# Sheet1.net
KiCad netlist of a schematic drawn in Altium Designer
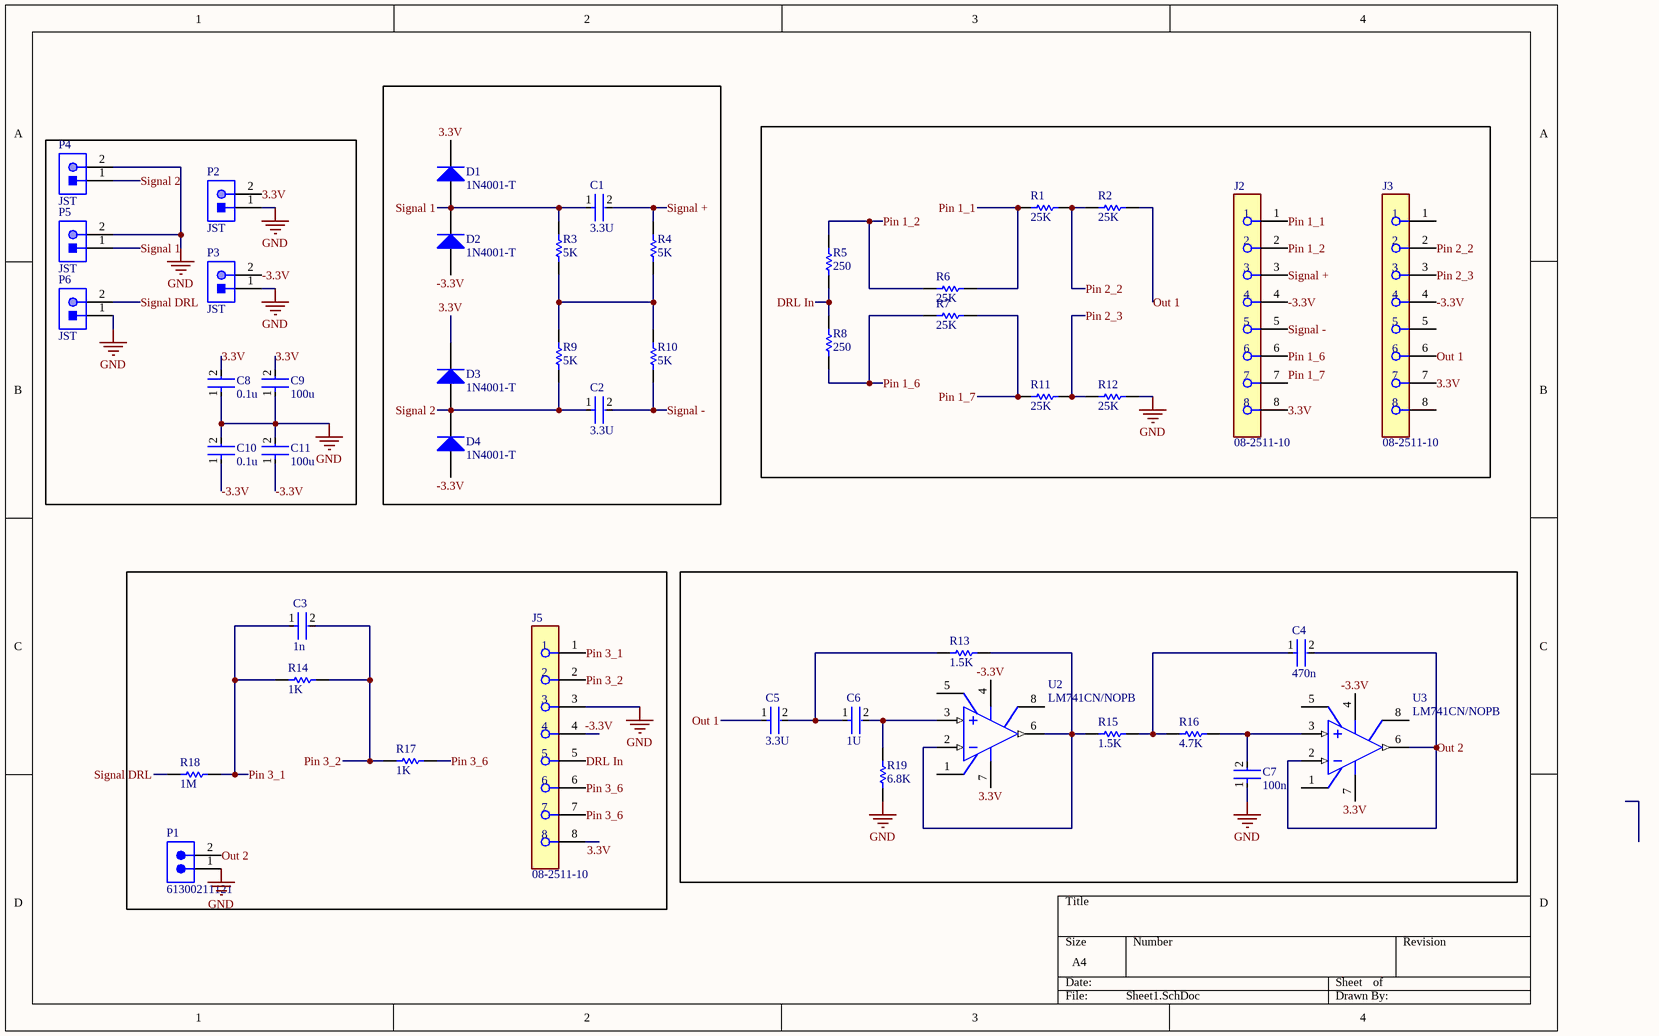
[diagram p0: Sheet1.SchDoc]

(export (version "E")
  (design (tool "Eeschema 10.0.6"))
  (components
    (comp (ref "C1")
      (value "3.3U")
      (footprint "FP-RCE3DB-MFG")
      (description "Cap Ceramic 10uF 25V X7R ±10% Radial 2.5mm +125°C Automotive Ammo Pack")
      (fields (field (name "TOLERANCE") "10%"))
      (libsource (lib "Altium Content Vault") (part "b4654b650e69147ec39a6b967a45e02"))
    )
    (comp (ref "C2")
      (value "3.3U")
      (footprint "FP-RCE3DB-MFG")
      (description "Cap Ceramic 10uF 25V X7R ±10% Radial 2.5mm +125°C Automotive Ammo Pack")
      (fields (field (name "TOLERANCE") "10%"))
      (libsource (lib "Altium Content Vault") (part "b4654b650e69147ec39a6b967a45e02"))
    )
    (comp (ref "C3")
      (value "1n")
      (footprint "FP-RCE3DB-MFG")
      (description "Cap Ceramic 10uF 25V X7R ±10% Radial 2.5mm +125°C Automotive Ammo Pack")
      (fields (field (name "TOLERANCE") "10%"))
      (libsource (lib "Altium Content Vault") (part "b4654b650e69147ec39a6b967a45e02"))
    )
    (comp (ref "C4")
      (value "470n")
      (footprint "FP-RCE3DB-MFG")
      (description "Cap Ceramic 10uF 25V X7R ±10% Radial 2.5mm +125°C Automotive Ammo Pack")
      (fields (field (name "TOLERANCE") "10%"))
      (libsource (lib "Altium Content Vault") (part "b4654b650e69147ec39a6b967a45e02"))
    )
    (comp (ref "C5")
      (value "3.3U")
      (footprint "FP-RCE3DB-MFG")
      (description "Cap Ceramic 10uF 25V X7R ±10% Radial 2.5mm +125°C Automotive Ammo Pack")
      (fields (field (name "TOLERANCE") "10%"))
      (libsource (lib "Altium Content Vault") (part "b4654b650e69147ec39a6b967a45e02"))
    )
    (comp (ref "C6")
      (value "1U")
      (footprint "FP-RCE3DB-MFG")
      (description "Cap Ceramic 10uF 25V X7R ±10% Radial 2.5mm +125°C Automotive Ammo Pack")
      (fields (field (name "TOLERANCE") "10%"))
      (libsource (lib "Altium Content Vault") (part "b4654b650e69147ec39a6b967a45e02"))
    )
    (comp (ref "C7")
      (value "100n")
      (footprint "FP-RCE3DB-MFG")
      (description "Cap Ceramic 10uF 25V X7R ±10% Radial 2.5mm +125°C Automotive Ammo Pack")
      (fields (field (name "TOLERANCE") "10%"))
      (libsource (lib "Altium Content Vault") (part "b4654b650e69147ec39a6b967a45e02"))
    )
    (comp (ref "C8")
      (value "0.1u")
      (footprint "FP-RCE3DB-MFG")
      (description "Cap Ceramic 10uF 25V X7R ±10% Radial 2.5mm +125°C Automotive Ammo Pack")
      (fields (field (name "TOLERANCE") "10%"))
      (libsource (lib "Altium Content Vault") (part "b4654b650e69147ec39a6b967a45e02"))
    )
    (comp (ref "C9")
      (value "100u")
      (footprint "FP-RCE3DB-MFG")
      (description "Cap Ceramic 10uF 25V X7R ±10% Radial 2.5mm +125°C Automotive Ammo Pack")
      (fields (field (name "TOLERANCE") "10%"))
      (libsource (lib "Altium Content Vault") (part "b4654b650e69147ec39a6b967a45e02"))
    )
    (comp (ref "C10")
      (value "0.1u")
      (footprint "FP-RCE3DB-MFG")
      (description "Cap Ceramic 10uF 25V X7R ±10% Radial 2.5mm +125°C Automotive Ammo Pack")
      (fields (field (name "TOLERANCE") "10%"))
      (libsource (lib "Altium Content Vault") (part "b4654b650e69147ec39a6b967a45e02"))
    )
    (comp (ref "C11")
      (value "100u")
      (footprint "FP-RCE3DB-MFG")
      (description "Cap Ceramic 10uF 25V X7R ±10% Radial 2.5mm +125°C Automotive Ammo Pack")
      (fields (field (name "TOLERANCE") "10%"))
      (libsource (lib "Altium Content Vault") (part "b4654b650e69147ec39a6b967a45e02"))
    )
    (comp (ref "D1")
      (value "1N4001-T")
      (footprint "DIOD-DO-41-P-2_V")
      (description "1.0 A Rectifier, 15 pF, 50 V, -65 to 150 degC, 2-Pin DO-41 Plastic, RoHS, Tape and Reel")
      (fields (field (name "MANUFACTURER") "Diodes Inc"))
      (libsource (lib "Altium Content Vault") (part "DIOD-D-A1K2-2"))
    )
    (comp (ref "D2")
      (value "1N4001-T")
      (footprint "DIOD-DO-41-P-2_V")
      (description "1.0 A Rectifier, 15 pF, 50 V, -65 to 150 degC, 2-Pin DO-41 Plastic, RoHS, Tape and Reel")
      (fields (field (name "MANUFACTURER") "Diodes Inc"))
      (libsource (lib "Altium Content Vault") (part "DIOD-D-A1K2-2"))
    )
    (comp (ref "D3")
      (value "1N4001-T")
      (footprint "DIOD-DO-41-P-2_V")
      (description "1.0 A Rectifier, 15 pF, 50 V, -65 to 150 degC, 2-Pin DO-41 Plastic, RoHS, Tape and Reel")
      (fields (field (name "MANUFACTURER") "Diodes Inc"))
      (libsource (lib "Altium Content Vault") (part "DIOD-D-A1K2-2"))
    )
    (comp (ref "D4")
      (value "1N4001-T")
      (footprint "DIOD-DO-41-P-2_V")
      (description "1.0 A Rectifier, 15 pF, 50 V, -65 to 150 degC, 2-Pin DO-41 Plastic, RoHS, Tape and Reel")
      (fields (field (name "MANUFACTURER") "Diodes Inc"))
      (libsource (lib "Altium Content Vault") (part "DIOD-D-A1K2-2"))
    )
    (comp (ref "J2")
      (value "08-2511-10")
      (footprint "FP-08-2511-10-MFG")
      (description "CONN IC DIP SOCKET 8POS TIN")
      (fields
        (field (name "MANUFACTURER") "Aries Electronics")
        (field (name "OCTOPART") "https://octopart.com/08-2511-10-aries-767661")
      )
      (libsource (lib "Altium Content Vault") (part "b0a0b555dd3abf3683e7c330df25cc4"))
    )
    (comp (ref "J3")
      (value "08-2511-10")
      (footprint "FP-08-2511-10-MFG")
      (description "CONN IC DIP SOCKET 8POS TIN")
      (fields
        (field (name "MANUFACTURER") "Aries Electronics")
        (field (name "OCTOPART") "https://octopart.com/08-2511-10-aries-767661")
      )
      (libsource (lib "Altium Content Vault") (part "b0a0b555dd3abf3683e7c330df25cc4"))
    )
    (comp (ref "J5")
      (value "08-2511-10")
      (footprint "FP-08-2511-10-MFG")
      (description "CONN IC DIP SOCKET 8POS TIN")
      (fields
        (field (name "MANUFACTURER") "Aries Electronics")
        (field (name "OCTOPART") "https://octopart.com/08-2511-10-aries-767661")
      )
      (libsource (lib "Altium Content Vault") (part "b0a0b555dd3abf3683e7c330df25cc4"))
    )
    (comp (ref "P1")
      (value "61300211121")
      (footprint "61300211121")
      (libsource (lib "Altium Content Vault") (part "Header_Male_1R_02P"))
    )
    (comp (ref "P2")
      (value "JST")
      (footprint "JST-S2B-PH-K-S_V")
      (fields (field (name "TOLERANCE") "20%"))
      (libsource (lib "Altium Content Vault") (part "CN-1P-M-R2"))
    )
    (comp (ref "P3")
      (value "JST")
      (footprint "JST-S2B-PH-K-S_V")
      (fields (field (name "TOLERANCE") "20%"))
      (libsource (lib "Altium Content Vault") (part "CN-1P-M-R2"))
    )
    (comp (ref "P4")
      (value "JST")
      (footprint "JST-S2B-PH-K-S_V")
      (fields (field (name "TOLERANCE") "20%"))
      (libsource (lib "Altium Content Vault") (part "CN-1P-M-R2"))
    )
    (comp (ref "P5")
      (value "JST")
      (footprint "JST-S2B-PH-K-S_V")
      (fields (field (name "TOLERANCE") "20%"))
      (libsource (lib "Altium Content Vault") (part "CN-1P-M-R2"))
    )
    (comp (ref "P6")
      (value "JST")
      (footprint "JST-S2B-PH-K-S_V")
      (fields (field (name "TOLERANCE") "20%"))
      (libsource (lib "Altium Content Vault") (part "CN-1P-M-R2"))
    )
    (comp (ref "R1")
      (value "25K")
      (footprint "RESA60-630X240")
      (description "Axial Resistor, 1 KOhm, +/- 1%, 250 mW, -55 to 155 degC, 2-Pin THD, RoHS, Bulk")
      (fields (field (name "TOLERANCE") "1%"))
      (libsource (lib "Altium Content Vault") (part "RES-2"))
    )
    (comp (ref "R2")
      (value "25K")
      (footprint "RESA60-630X240")
      (description "Axial Resistor, 1 KOhm, +/- 1%, 250 mW, -55 to 155 degC, 2-Pin THD, RoHS, Bulk")
      (fields (field (name "TOLERANCE") "1%"))
      (libsource (lib "Altium Content Vault") (part "RES-2"))
    )
    (comp (ref "R3")
      (value "5K")
      (footprint "RESA60-630X240")
      (description "Axial Resistor, 1 KOhm, +/- 1%, 250 mW, -55 to 155 degC, 2-Pin THD, RoHS, Bulk")
      (fields (field (name "TOLERANCE") "1%"))
      (libsource (lib "Altium Content Vault") (part "RES-2"))
    )
    (comp (ref "R4")
      (value "5K")
      (footprint "RESA60-630X240")
      (description "Axial Resistor, 1 KOhm, +/- 1%, 250 mW, -55 to 155 degC, 2-Pin THD, RoHS, Bulk")
      (fields (field (name "TOLERANCE") "1%"))
      (libsource (lib "Altium Content Vault") (part "RES-2"))
    )
    (comp (ref "R5")
      (value "250")
      (footprint "RESA60-630X240")
      (description "Axial Resistor, 1 KOhm, +/- 1%, 250 mW, -55 to 155 degC, 2-Pin THD, RoHS, Bulk")
      (fields (field (name "TOLERANCE") "1%"))
      (libsource (lib "Altium Content Vault") (part "RES-2"))
    )
    (comp (ref "R6")
      (value "25K")
      (footprint "RESA60-630X240")
      (description "Axial Resistor, 1 KOhm, +/- 1%, 250 mW, -55 to 155 degC, 2-Pin THD, RoHS, Bulk")
      (fields (field (name "TOLERANCE") "1%"))
      (libsource (lib "Altium Content Vault") (part "RES-2"))
    )
    (comp (ref "R7")
      (value "25K")
      (footprint "RESA60-630X240")
      (description "Axial Resistor, 1 KOhm, +/- 1%, 250 mW, -55 to 155 degC, 2-Pin THD, RoHS, Bulk")
      (fields (field (name "TOLERANCE") "1%"))
      (libsource (lib "Altium Content Vault") (part "RES-2"))
    )
    (comp (ref "R8")
      (value "250")
      (footprint "RESA60-630X240")
      (description "Axial Resistor, 1 KOhm, +/- 1%, 250 mW, -55 to 155 degC, 2-Pin THD, RoHS, Bulk")
      (fields (field (name "TOLERANCE") "1%"))
      (libsource (lib "Altium Content Vault") (part "RES-2"))
    )
    (comp (ref "R9")
      (value "5K")
      (footprint "RESA60-630X240")
      (description "Axial Resistor, 1 KOhm, +/- 1%, 250 mW, -55 to 155 degC, 2-Pin THD, RoHS, Bulk")
      (fields (field (name "TOLERANCE") "1%"))
      (libsource (lib "Altium Content Vault") (part "RES-2"))
    )
    (comp (ref "R10")
      (value "5K")
      (footprint "RESA60-630X240")
      (description "Axial Resistor, 1 KOhm, +/- 1%, 250 mW, -55 to 155 degC, 2-Pin THD, RoHS, Bulk")
      (fields (field (name "TOLERANCE") "1%"))
      (libsource (lib "Altium Content Vault") (part "RES-2"))
    )
    (comp (ref "R11")
      (value "25K")
      (footprint "RESA60-630X240")
      (description "Axial Resistor, 1 KOhm, +/- 1%, 250 mW, -55 to 155 degC, 2-Pin THD, RoHS, Bulk")
      (fields (field (name "TOLERANCE") "1%"))
      (libsource (lib "Altium Content Vault") (part "RES-2"))
    )
    (comp (ref "R12")
      (value "25K")
      (footprint "RESA60-630X240")
      (description "Axial Resistor, 1 KOhm, +/- 1%, 250 mW, -55 to 155 degC, 2-Pin THD, RoHS, Bulk")
      (fields (field (name "TOLERANCE") "1%"))
      (libsource (lib "Altium Content Vault") (part "RES-2"))
    )
    (comp (ref "R13")
      (value "1.5K")
      (footprint "RESA60-630X240")
      (description "Axial Resistor, 1 KOhm, +/- 1%, 250 mW, -55 to 155 degC, 2-Pin THD, RoHS, Bulk")
      (fields (field (name "TOLERANCE") "1%"))
      (libsource (lib "Altium Content Vault") (part "RES-2"))
    )
    (comp (ref "R14")
      (value "1K")
      (footprint "RESA60-630X240")
      (description "Axial Resistor, 1 KOhm, +/- 1%, 250 mW, -55 to 155 degC, 2-Pin THD, RoHS, Bulk")
      (fields (field (name "TOLERANCE") "1%"))
      (libsource (lib "Altium Content Vault") (part "RES-2"))
    )
    (comp (ref "R15")
      (value "1.5K")
      (footprint "RESA60-630X240")
      (description "Axial Resistor, 1 KOhm, +/- 1%, 250 mW, -55 to 155 degC, 2-Pin THD, RoHS, Bulk")
      (fields (field (name "TOLERANCE") "1%"))
      (libsource (lib "Altium Content Vault") (part "RES-2"))
    )
    (comp (ref "R16")
      (value "4.7K")
      (footprint "RESA60-630X240")
      (description "Axial Resistor, 1 KOhm, +/- 1%, 250 mW, -55 to 155 degC, 2-Pin THD, RoHS, Bulk")
      (fields (field (name "TOLERANCE") "1%"))
      (libsource (lib "Altium Content Vault") (part "RES-2"))
    )
    (comp (ref "R17")
      (value "1K")
      (footprint "RESA60-630X240")
      (description "Axial Resistor, 1 KOhm, +/- 1%, 250 mW, -55 to 155 degC, 2-Pin THD, RoHS, Bulk")
      (fields (field (name "TOLERANCE") "1%"))
      (libsource (lib "Altium Content Vault") (part "RES-2"))
    )
    (comp (ref "R18")
      (value "1M")
      (footprint "RESA60-630X240")
      (description "Axial Resistor, 1 KOhm, +/- 1%, 250 mW, -55 to 155 degC, 2-Pin THD, RoHS, Bulk")
      (fields (field (name "TOLERANCE") "1%"))
      (libsource (lib "Altium Content Vault") (part "RES-2"))
    )
    (comp (ref "R19")
      (value "6.8K")
      (footprint "RESA60-630X240")
      (description "Axial Resistor, 1 KOhm, +/- 1%, 250 mW, -55 to 155 degC, 2-Pin THD, RoHS, Bulk")
      (fields (field (name "TOLERANCE") "1%"))
      (libsource (lib "Altium Content Vault") (part "RES-2"))
    )
    (comp (ref "U2")
      (value "LM741CN/NOPB")
      (footprint "P0008A")
      (description "Operational Amplifier, 8-pin MDIP, Pb-Free")
      (fields (field (name "MANUFACTURER") "Texas Instruments"))
      (libsource (lib "Altium Content Vault") (part "AMP-OPA-LM741-8"))
    )
    (comp (ref "U3")
      (value "LM741CN/NOPB")
      (footprint "P0008A")
      (description "Operational Amplifier, 8-pin MDIP, Pb-Free")
      (fields (field (name "MANUFACTURER") "Texas Instruments"))
      (libsource (lib "Altium Content Vault") (part "AMP-OPA-LM741-8"))
    )
  )
  (nets
    (net (code "1") (name "/-3.3V") (class "Default")
      (node (ref "C10") (pin "1") (pinfunction "1_1") (pintype "passive"))
      (node (ref "C11") (pin "1") (pinfunction "1_1") (pintype "passive"))
      (node (ref "D2") (pin "1") (pinfunction "A_1") (pintype "passive"))
      (node (ref "D4") (pin "1") (pinfunction "A_1") (pintype "passive"))
      (node (ref "J2") (pin "4") (pinfunction "4_4") (pintype "passive"))
      (node (ref "J3") (pin "4") (pinfunction "4_4") (pintype "passive"))
      (node (ref "J5") (pin "4") (pinfunction "4_4") (pintype "passive"))
      (node (ref "P3") (pin "2") (pinfunction "2_2") (pintype "passive"))
      (node (ref "U2") (pin "4") (pinfunction "V-_4") (pintype "power_in"))
      (node (ref "U3") (pin "4") (pinfunction "V-_4") (pintype "power_in"))
    )
    (net (code "2") (name "/3.3V") (class "Default")
      (node (ref "C8") (pin "2") (pinfunction "2_2") (pintype "passive"))
      (node (ref "C9") (pin "2") (pinfunction "2_2") (pintype "passive"))
      (node (ref "D1") (pin "2") (pinfunction "K_2") (pintype "passive"))
      (node (ref "D3") (pin "2") (pinfunction "K_2") (pintype "passive"))
      (node (ref "J2") (pin "8") (pinfunction "8_8") (pintype "passive"))
      (node (ref "J3") (pin "7") (pinfunction "7_7") (pintype "passive"))
      (node (ref "J5") (pin "8") (pinfunction "8_8") (pintype "passive"))
      (node (ref "P2") (pin "2") (pinfunction "2_2") (pintype "passive"))
      (node (ref "U2") (pin "7") (pinfunction "V+_7") (pintype "power_in"))
      (node (ref "U3") (pin "7") (pinfunction "V+_7") (pintype "power_in"))
    )
    (net (code "3") (name "/DRL In") (class "Default")
      (node (ref "J5") (pin "5") (pinfunction "5_5") (pintype "passive"))
      (node (ref "R5") (pin "2") (pinfunction "2_2") (pintype "passive"))
      (node (ref "R8") (pin "1") (pinfunction "1_1") (pintype "passive"))
    )
    (net (code "4") (name "/Out 1") (class "Default")
      (node (ref "C5") (pin "1") (pinfunction "1_1") (pintype "passive"))
      (node (ref "J3") (pin "6") (pinfunction "6_6") (pintype "passive"))
      (node (ref "R2") (pin "1") (pinfunction "1_1") (pintype "passive"))
    )
    (net (code "5") (name "/Out 2") (class "Default")
      (node (ref "C4") (pin "2") (pinfunction "2_2") (pintype "passive"))
      (node (ref "P1") (pin "2") (pinfunction "2_2") (pintype "passive"))
      (node (ref "U3") (pin "2") (pinfunction "IN-_2") (pintype "input"))
      (node (ref "U3") (pin "6") (pinfunction "OUT_6") (pintype "output"))
    )
    (net (code "6") (name "/Pin 1_1") (class "Default")
      (node (ref "J2") (pin "1") (pinfunction "1_1") (pintype "passive"))
      (node (ref "R1") (pin "2") (pinfunction "2_2") (pintype "passive"))
      (node (ref "R6") (pin "1") (pinfunction "1_1") (pintype "passive"))
    )
    (net (code "7") (name "/Pin 1_2") (class "Default")
      (node (ref "J2") (pin "2") (pinfunction "2_2") (pintype "passive"))
      (node (ref "R5") (pin "1") (pinfunction "1_1") (pintype "passive"))
      (node (ref "R6") (pin "2") (pinfunction "2_2") (pintype "passive"))
    )
    (net (code "8") (name "/Pin 1_6") (class "Default")
      (node (ref "J2") (pin "6") (pinfunction "6_6") (pintype "passive"))
      (node (ref "R7") (pin "2") (pinfunction "2_2") (pintype "passive"))
      (node (ref "R8") (pin "2") (pinfunction "2_2") (pintype "passive"))
    )
    (net (code "9") (name "/Pin 1_7") (class "Default")
      (node (ref "J2") (pin "7") (pinfunction "7_7") (pintype "passive"))
      (node (ref "R11") (pin "2") (pinfunction "2_2") (pintype "passive"))
      (node (ref "R7") (pin "1") (pinfunction "1_1") (pintype "passive"))
    )
    (net (code "10") (name "/Pin 2_2") (class "Default")
      (node (ref "J3") (pin "2") (pinfunction "2_2") (pintype "passive"))
      (node (ref "R1") (pin "1") (pinfunction "1_1") (pintype "passive"))
      (node (ref "R2") (pin "2") (pinfunction "2_2") (pintype "passive"))
    )
    (net (code "11") (name "/Pin 2_3") (class "Default")
      (node (ref "J3") (pin "3") (pinfunction "3_3") (pintype "passive"))
      (node (ref "R11") (pin "1") (pinfunction "1_1") (pintype "passive"))
      (node (ref "R12") (pin "2") (pinfunction "2_2") (pintype "passive"))
    )
    (net (code "12") (name "/Pin 3_1") (class "Default")
      (node (ref "C3") (pin "1") (pinfunction "1_1") (pintype "passive"))
      (node (ref "J5") (pin "1") (pinfunction "1_1") (pintype "passive"))
      (node (ref "R14") (pin "2") (pinfunction "2_2") (pintype "passive"))
      (node (ref "R18") (pin "1") (pinfunction "1_1") (pintype "passive"))
    )
    (net (code "13") (name "/Pin 3_2") (class "Default")
      (node (ref "C3") (pin "2") (pinfunction "2_2") (pintype "passive"))
      (node (ref "J5") (pin "2") (pinfunction "2_2") (pintype "passive"))
      (node (ref "R14") (pin "1") (pinfunction "1_1") (pintype "passive"))
      (node (ref "R17") (pin "2") (pinfunction "2_2") (pintype "passive"))
    )
    (net (code "14") (name "/Pin 3_6") (class "Default")
      (node (ref "J5") (pin "6") (pinfunction "6_6") (pintype "passive"))
      (node (ref "J5") (pin "7") (pinfunction "7_7") (pintype "passive"))
      (node (ref "R17") (pin "1") (pinfunction "1_1") (pintype "passive"))
    )
    (net (code "15") (name "/Signal +") (class "Default")
      (node (ref "C1") (pin "2") (pinfunction "2_2") (pintype "passive"))
      (node (ref "J2") (pin "3") (pinfunction "3_3") (pintype "passive"))
      (node (ref "R4") (pin "2") (pinfunction "2_2") (pintype "passive"))
    )
    (net (code "16") (name "/Signal -") (class "Default")
      (node (ref "C2") (pin "2") (pinfunction "2_2") (pintype "passive"))
      (node (ref "J2") (pin "5") (pinfunction "5_5") (pintype "passive"))
      (node (ref "R10") (pin "1") (pinfunction "1_1") (pintype "passive"))
    )
    (net (code "17") (name "/Signal 1") (class "Default")
      (node (ref "C1") (pin "1") (pinfunction "1_1") (pintype "passive"))
      (node (ref "D1") (pin "1") (pinfunction "A_1") (pintype "passive"))
      (node (ref "D2") (pin "2") (pinfunction "K_2") (pintype "passive"))
      (node (ref "P5") (pin "1") (pinfunction "1_1") (pintype "passive"))
      (node (ref "R3") (pin "2") (pinfunction "2_2") (pintype "passive"))
    )
    (net (code "18") (name "/Signal 2") (class "Default")
      (node (ref "C2") (pin "1") (pinfunction "1_1") (pintype "passive"))
      (node (ref "D3") (pin "1") (pinfunction "A_1") (pintype "passive"))
      (node (ref "D4") (pin "2") (pinfunction "K_2") (pintype "passive"))
      (node (ref "P4") (pin "1") (pinfunction "1_1") (pintype "passive"))
      (node (ref "R9") (pin "1") (pinfunction "1_1") (pintype "passive"))
    )
    (net (code "19") (name "/Signal DRL") (class "Default")
      (node (ref "P6") (pin "2") (pinfunction "2_2") (pintype "passive"))
      (node (ref "R18") (pin "2") (pinfunction "2_2") (pintype "passive"))
    )
    (net (code "20") (name "GND") (class "Default")
      (node (ref "C10") (pin "2") (pinfunction "2_2") (pintype "passive"))
      (node (ref "C11") (pin "2") (pinfunction "2_2") (pintype "passive"))
      (node (ref "C7") (pin "1") (pinfunction "1_1") (pintype "passive"))
      (node (ref "C8") (pin "1") (pinfunction "1_1") (pintype "passive"))
      (node (ref "C9") (pin "1") (pinfunction "1_1") (pintype "passive"))
      (node (ref "J5") (pin "3") (pinfunction "3_3") (pintype "passive"))
      (node (ref "P1") (pin "1") (pinfunction "1_1") (pintype "passive"))
      (node (ref "P2") (pin "1") (pinfunction "1_1") (pintype "passive"))
      (node (ref "P3") (pin "1") (pinfunction "1_1") (pintype "passive"))
      (node (ref "P4") (pin "2") (pinfunction "2_2") (pintype "passive"))
      (node (ref "P5") (pin "2") (pinfunction "2_2") (pintype "passive"))
      (node (ref "P6") (pin "1") (pinfunction "1_1") (pintype "passive"))
      (node (ref "R12") (pin "1") (pinfunction "1_1") (pintype "passive"))
      (node (ref "R19") (pin "2") (pinfunction "2_2") (pintype "passive"))
    )
    (net (code "21") (name "Net-(C4-Pad1)") (class "Default")
      (node (ref "C4") (pin "1") (pinfunction "1_1") (pintype "passive"))
      (node (ref "R15") (pin "1") (pinfunction "1_1") (pintype "passive"))
      (node (ref "R16") (pin "2") (pinfunction "2_2") (pintype "passive"))
    )
    (net (code "22") (name "Net-(C5-Pad2)") (class "Default")
      (node (ref "C5") (pin "2") (pinfunction "2_2") (pintype "passive"))
      (node (ref "C6") (pin "1") (pinfunction "1_1") (pintype "passive"))
      (node (ref "R13") (pin "2") (pinfunction "2_2") (pintype "passive"))
    )
    (net (code "23") (name "Net-(R10-Pad2)") (class "Default")
      (node (ref "R10") (pin "2") (pinfunction "2_2") (pintype "passive"))
      (node (ref "R3") (pin "1") (pinfunction "1_1") (pintype "passive"))
      (node (ref "R4") (pin "1") (pinfunction "1_1") (pintype "passive"))
      (node (ref "R9") (pin "2") (pinfunction "2_2") (pintype "passive"))
    )
    (net (code "24") (name "Net-(U2-IN+)") (class "Default")
      (node (ref "C6") (pin "2") (pinfunction "2_2") (pintype "passive"))
      (node (ref "R19") (pin "1") (pinfunction "1_1") (pintype "passive"))
      (node (ref "U2") (pin "3") (pinfunction "IN+_3") (pintype "input"))
    )
    (net (code "25") (name "Net-(U2-IN-)") (class "Default")
      (node (ref "R13") (pin "1") (pinfunction "1_1") (pintype "passive"))
      (node (ref "R15") (pin "2") (pinfunction "2_2") (pintype "passive"))
      (node (ref "U2") (pin "2") (pinfunction "IN-_2") (pintype "input"))
      (node (ref "U2") (pin "6") (pinfunction "OUT_6") (pintype "output"))
    )
    (net (code "26") (name "Net-(U3-IN+)") (class "Default")
      (node (ref "C7") (pin "2") (pinfunction "2_2") (pintype "passive"))
      (node (ref "R16") (pin "1") (pinfunction "1_1") (pintype "passive"))
      (node (ref "U3") (pin "3") (pinfunction "IN+_3") (pintype "input"))
    )
    (net (code "27") (name "unconnected-(J3-Pad1)") (class "Default")
      (node (ref "J3") (pin "1") (pinfunction "1_1") (pintype "passive"))
    )
    (net (code "28") (name "unconnected-(J3-Pad5)") (class "Default")
      (node (ref "J3") (pin "5") (pinfunction "5_5") (pintype "passive"))
    )
    (net (code "29") (name "unconnected-(J3-Pad8)") (class "Default")
      (node (ref "J3") (pin "8") (pinfunction "8_8") (pintype "passive"))
    )
    (net (code "30") (name "unconnected-(U2-NC-Pad8)") (class "Default")
      (node (ref "U2") (pin "8") (pinfunction "NC_8") (pintype "passive"))
    )
    (net (code "31") (name "unconnected-(U2-OFS_NULL-Pad1)") (class "Default")
      (node (ref "U2") (pin "1") (pinfunction "OFS_NULL_1") (pintype "passive"))
    )
    (net (code "32") (name "unconnected-(U2-OFS_NULL-Pad5)") (class "Default")
      (node (ref "U2") (pin "5") (pinfunction "OFS_NULL_5") (pintype "passive"))
    )
    (net (code "33") (name "unconnected-(U3-NC-Pad8)") (class "Default")
      (node (ref "U3") (pin "8") (pinfunction "NC_8") (pintype "passive"))
    )
    (net (code "34") (name "unconnected-(U3-OFS_NULL-Pad1)") (class "Default")
      (node (ref "U3") (pin "1") (pinfunction "OFS_NULL_1") (pintype "passive"))
    )
    (net (code "35") (name "unconnected-(U3-OFS_NULL-Pad5)") (class "Default")
      (node (ref "U3") (pin "5") (pinfunction "OFS_NULL_5") (pintype "passive"))
    )
  )
)
